# VidorCameraLock.net
KiCad netlist of a schematic drawn in EAGLE
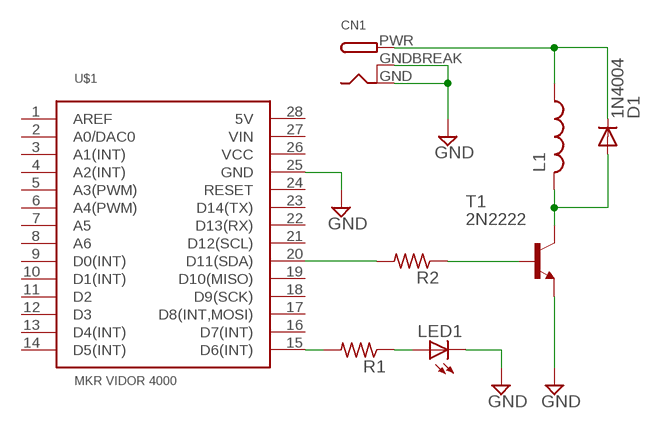
[diagram p0: schematic, sheet 1]

(export (version "E")
  (design (tool "Eeschema 10.0.6"))
  (components
    (comp (ref "CN1")
      (value "DCBARRELPTH")
      (footprint "eagle-import:DCJACK_2MM_PTH")
      (libsource (lib "eagle-import") (part "DCBARRELPTH"))
    )
    (comp (ref "D1")
      (value "1N4004")
      (footprint "eagle-import:DO41-10")
      (libsource (lib "eagle-import") (part "1N4004"))
    )
    (comp (ref "L1")
      (value "L-US0204/7")
      (footprint "eagle-import:0204_7")
      (libsource (lib "eagle-import") (part "L-US0204/7"))
    )
    (comp (ref "LED1")
      (value "LED3MM")
      (footprint "eagle-import:LED3MM")
      (libsource (lib "eagle-import") (part "LED3MM"))
    )
    (comp (ref "R1")
      (value "R-US_0207/5V")
      (footprint "eagle-import:0207_5V")
      (libsource (lib "eagle-import") (part "R-US_0207/5V"))
    )
    (comp (ref "R2")
      (value "R-US_0207/5V")
      (footprint "eagle-import:0207_5V")
      (libsource (lib "eagle-import") (part "R-US_0207/5V"))
    )
    (comp (ref "T1")
      (value "2N2222")
      (footprint "eagle-import:TO92-EBC-OVAL")
      (libsource (lib "eagle-import") (part "2N2222"))
    )
    (comp (ref "U$1")
      (value "MKR VIDOR 4000")
      (footprint "eagle-import:MKR1000-SOCKET")
      (libsource (lib "eagle-import") (part "MKR1000"))
    )
  )
  (nets
    (net (code "1") (name "GND") (class "Default")
      (node (ref "CN1") (pin "GND") (pinfunction "GND_GND") (pintype "power_in"))
      (node (ref "CN1") (pin "GNDBREAK") (pinfunction "GNDBREAK_GNDBREAK") (pintype "power_in"))
      (node (ref "LED1") (pin "K") (pinfunction "C_K") (pintype "passive"))
      (node (ref "T1") (pin "E") (pinfunction "E_E") (pintype "passive"))
      (node (ref "U$1") (pin "25") (pinfunction "GND_25") (pintype "bidirectional"))
    )
    (net (code "2") (name "Net-(CN1-PadPWR)") (class "Default")
      (node (ref "CN1") (pin "PWR") (pinfunction "PWR_PWR") (pintype "power_in"))
      (node (ref "D1") (pin "C") (pinfunction "C_C") (pintype "passive"))
      (node (ref "L1") (pin "1") (pinfunction "1_1") (pintype "passive"))
    )
    (net (code "3") (name "Net-(D1-PadA)") (class "Default")
      (node (ref "D1") (pin "A") (pinfunction "A_A") (pintype "passive"))
      (node (ref "L1") (pin "2") (pinfunction "2_2") (pintype "passive"))
      (node (ref "T1") (pin "C") (pinfunction "C_C") (pintype "passive"))
    )
    (net (code "4") (name "Net-(LED1-PadA)") (class "Default")
      (node (ref "LED1") (pin "A") (pinfunction "A_A") (pintype "passive"))
      (node (ref "R1") (pin "1") (pinfunction "1_1") (pintype "passive"))
    )
    (net (code "5") (name "Net-(R2-Pad1)") (class "Default")
      (node (ref "R2") (pin "1") (pinfunction "1_1") (pintype "passive"))
      (node (ref "T1") (pin "B") (pinfunction "B_B") (pintype "passive"))
    )
    (net (code "6") (name "Net-(U$1-D6(INT))") (class "Default")
      (node (ref "R1") (pin "2") (pinfunction "2_2") (pintype "passive"))
      (node (ref "U$1") (pin "15") (pinfunction "D6(INT)_15") (pintype "bidirectional"))
    )
    (net (code "7") (name "Net-(U$1-D11(SDA))") (class "Default")
      (node (ref "R2") (pin "2") (pinfunction "2_2") (pintype "passive"))
      (node (ref "U$1") (pin "20") (pinfunction "D11(SDA)_20") (pintype "bidirectional"))
    )
    (net (code "8") (name "unconnected-(U$1-5V-Pad28)") (class "Default")
      (node (ref "U$1") (pin "28") (pinfunction "5V_28") (pintype "bidirectional"))
    )
    (net (code "9") (name "unconnected-(U$1-A0{slash}DAC0-Pad2)") (class "Default")
      (node (ref "U$1") (pin "2") (pinfunction "A0/DAC0_2") (pintype "bidirectional"))
    )
    (net (code "10") (name "unconnected-(U$1-A1(INT)-Pad3)") (class "Default")
      (node (ref "U$1") (pin "3") (pinfunction "A1(INT)_3") (pintype "bidirectional"))
    )
    (net (code "11") (name "unconnected-(U$1-A2(INT)-Pad4)") (class "Default")
      (node (ref "U$1") (pin "4") (pinfunction "A2(INT)_4") (pintype "bidirectional"))
    )
    (net (code "12") (name "unconnected-(U$1-A3(PWM)-Pad5)") (class "Default")
      (node (ref "U$1") (pin "5") (pinfunction "A3(PWM)_5") (pintype "bidirectional"))
    )
    (net (code "13") (name "unconnected-(U$1-A4(PWM)-Pad6)") (class "Default")
      (node (ref "U$1") (pin "6") (pinfunction "A4(PWM)_6") (pintype "bidirectional"))
    )
    (net (code "14") (name "unconnected-(U$1-A5-Pad7)") (class "Default")
      (node (ref "U$1") (pin "7") (pinfunction "A5_7") (pintype "bidirectional"))
    )
    (net (code "15") (name "unconnected-(U$1-A6-Pad8)") (class "Default")
      (node (ref "U$1") (pin "8") (pinfunction "A6_8") (pintype "bidirectional"))
    )
    (net (code "16") (name "unconnected-(U$1-AREF-Pad1)") (class "Default")
      (node (ref "U$1") (pin "1") (pinfunction "AREF_1") (pintype "bidirectional"))
    )
    (net (code "17") (name "unconnected-(U$1-D0(INT)-Pad9)") (class "Default")
      (node (ref "U$1") (pin "9") (pinfunction "D0(INT)_9") (pintype "bidirectional"))
    )
    (net (code "18") (name "unconnected-(U$1-D1(INT)-Pad10)") (class "Default")
      (node (ref "U$1") (pin "10") (pinfunction "D1(INT)_10") (pintype "bidirectional"))
    )
    (net (code "19") (name "unconnected-(U$1-D2-Pad11)") (class "Default")
      (node (ref "U$1") (pin "11") (pinfunction "D2_11") (pintype "bidirectional"))
    )
    (net (code "20") (name "unconnected-(U$1-D3-Pad12)") (class "Default")
      (node (ref "U$1") (pin "12") (pinfunction "D3_12") (pintype "bidirectional"))
    )
    (net (code "21") (name "unconnected-(U$1-D4(INT)-Pad13)") (class "Default")
      (node (ref "U$1") (pin "13") (pinfunction "D4(INT)_13") (pintype "bidirectional"))
    )
    (net (code "22") (name "unconnected-(U$1-D5(INT)-Pad14)") (class "Default")
      (node (ref "U$1") (pin "14") (pinfunction "D5(INT)_14") (pintype "bidirectional"))
    )
    (net (code "23") (name "unconnected-(U$1-D7(INT)-Pad16)") (class "Default")
      (node (ref "U$1") (pin "16") (pinfunction "D7(INT)_16") (pintype "bidirectional"))
    )
    (net (code "24") (name "unconnected-(U$1-D8(INT,MOSI)-Pad17)") (class "Default")
      (node (ref "U$1") (pin "17") (pinfunction "D8(INT,MOSI)_17") (pintype "bidirectional"))
    )
    (net (code "25") (name "unconnected-(U$1-D9(SCK)-Pad18)") (class "Default")
      (node (ref "U$1") (pin "18") (pinfunction "D9(SCK)_18") (pintype "bidirectional"))
    )
    (net (code "26") (name "unconnected-(U$1-D10(MISO)-Pad19)") (class "Default")
      (node (ref "U$1") (pin "19") (pinfunction "D10(MISO)_19") (pintype "bidirectional"))
    )
    (net (code "27") (name "unconnected-(U$1-D12(SCL)-Pad21)") (class "Default")
      (node (ref "U$1") (pin "21") (pinfunction "D12(SCL)_21") (pintype "bidirectional"))
    )
    (net (code "28") (name "unconnected-(U$1-D13(RX)-Pad22)") (class "Default")
      (node (ref "U$1") (pin "22") (pinfunction "D13(RX)_22") (pintype "bidirectional"))
    )
    (net (code "29") (name "unconnected-(U$1-D14(TX)-Pad23)") (class "Default")
      (node (ref "U$1") (pin "23") (pinfunction "D14(TX)_23") (pintype "bidirectional"))
    )
    (net (code "30") (name "unconnected-(U$1-RESET-Pad24)") (class "Default")
      (node (ref "U$1") (pin "24") (pinfunction "RESET_24") (pintype "bidirectional"))
    )
    (net (code "31") (name "unconnected-(U$1-VCC-Pad26)") (class "Default")
      (node (ref "U$1") (pin "26") (pinfunction "VCC_26") (pintype "bidirectional"))
    )
    (net (code "32") (name "unconnected-(U$1-VIN-Pad27)") (class "Default")
      (node (ref "U$1") (pin "27") (pinfunction "VIN_27") (pintype "bidirectional"))
    )
  )
)
